# ARM-Cortex_M0.net
KiCad netlist of a schematic drawn in EAGLE
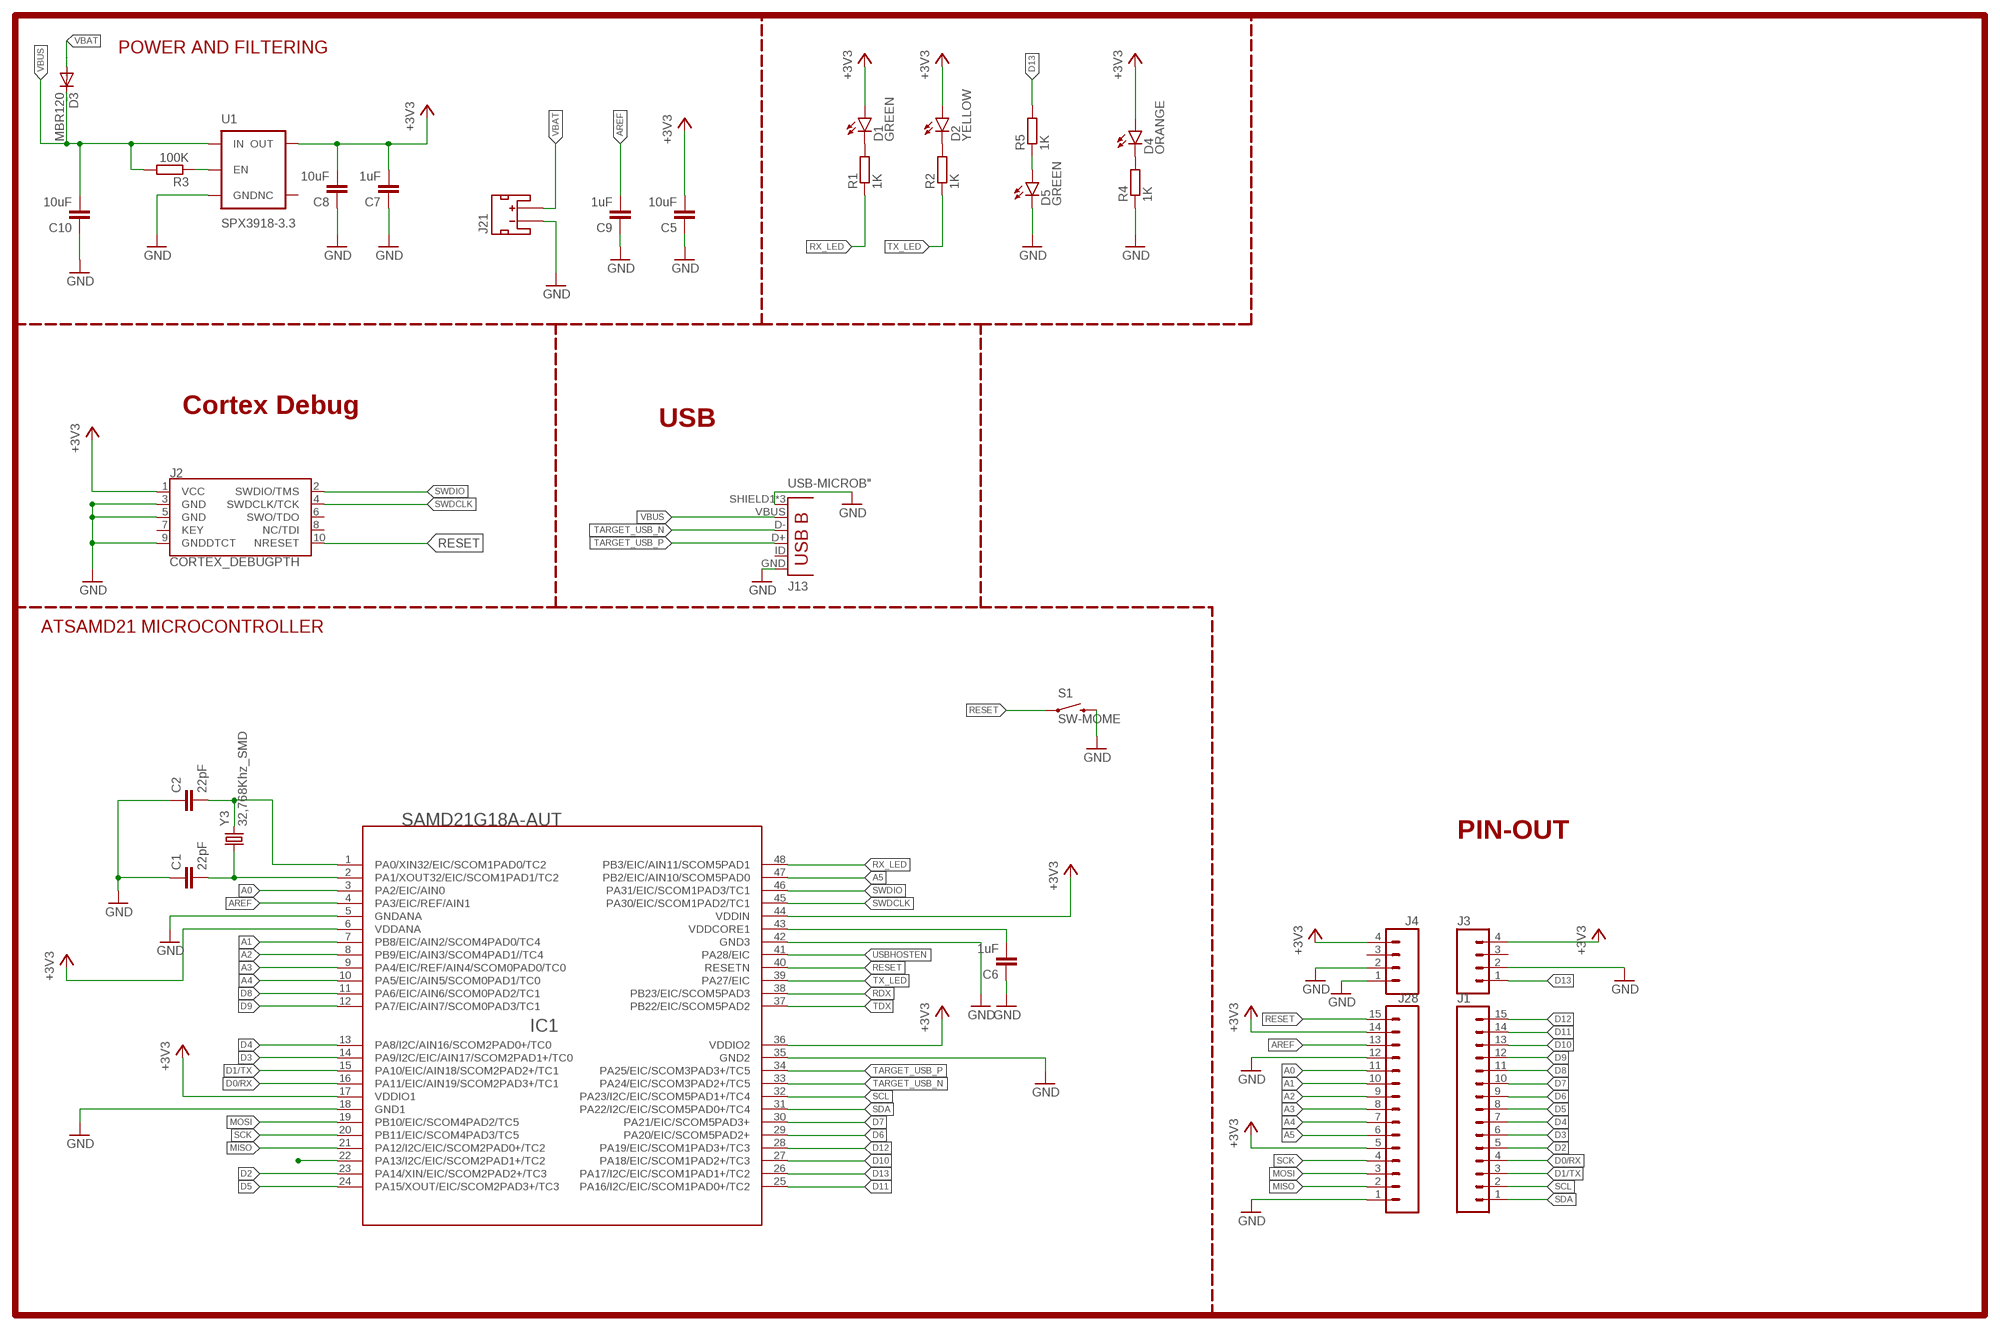
[diagram p0: schematic, sheet 1]

(export (version "E")
  (design (tool "Eeschema 10.0.6"))
  (components
    (comp (ref "C1")
      (value "22pF")
      (footprint "eagle-import:C0603")
      (libsource (lib "eagle-import") (part "C-EUC0603"))
    )
    (comp (ref "C2")
      (value "22pF")
      (footprint "eagle-import:C0603")
      (libsource (lib "eagle-import") (part "C-EUC0603"))
    )
    (comp (ref "C5")
      (value "10uF")
      (footprint "eagle-import:C0603")
      (libsource (lib "eagle-import") (part "C-EUC0603"))
    )
    (comp (ref "C6")
      (value "1uF")
      (footprint "eagle-import:C0603")
      (libsource (lib "eagle-import") (part "C-EUC0603"))
    )
    (comp (ref "C7")
      (value "1uF")
      (footprint "eagle-import:C0603")
      (libsource (lib "eagle-import") (part "C-EUC0603"))
    )
    (comp (ref "C8")
      (value "10uF")
      (footprint "eagle-import:C0603")
      (libsource (lib "eagle-import") (part "C-EUC0603"))
    )
    (comp (ref "C9")
      (value "1uF")
      (footprint "eagle-import:C0603")
      (libsource (lib "eagle-import") (part "C-EUC0603"))
    )
    (comp (ref "C10")
      (value "10uF")
      (footprint "eagle-import:C0603")
      (libsource (lib "eagle-import") (part "C-EUC0603"))
    )
    (comp (ref "D1")
      (value "GREEN")
      (footprint "eagle-import:LED-0603")
      (libsource (lib "eagle-import") (part "LED0603"))
    )
    (comp (ref "D2")
      (value "YELLOW")
      (footprint "eagle-import:LED-0603")
      (libsource (lib "eagle-import") (part "LED0603"))
    )
    (comp (ref "D3")
      (value "MBR120")
      (footprint "eagle-import:SOD-123_MINI-SMA")
      (libsource (lib "eagle-import") (part "CGRM400-G1"))
    )
    (comp (ref "D4")
      (value "ORANGE")
      (footprint "eagle-import:LED-0603")
      (libsource (lib "eagle-import") (part "LED0603"))
    )
    (comp (ref "D5")
      (value "GREEN")
      (footprint "eagle-import:LED-0603")
      (libsource (lib "eagle-import") (part "LED0603"))
    )
    (comp (ref "IC1")
      (value "SAMD21G18A-AUT")
      (footprint "eagle-import:TQFP48-7X7")
      (libsource (lib "eagle-import") (part "1792_SAMD21G18A-AUT"))
    )
    (comp (ref "J1")
      (value "M15")
      (footprint "eagle-import:1X15")
      (libsource (lib "eagle-import") (part "M15"))
    )
    (comp (ref "J2")
      (value "CORTEX_DEBUGPTH")
      (footprint "eagle-import:2X5-PTH-1.27MM")
      (libsource (lib "eagle-import") (part "CORTEX_DEBUGPTH"))
    )
    (comp (ref "J3")
      (value "M04NO_SILK_ALL_ROUND")
      (footprint "eagle-import:1X04_NO_SILK_ALL_ROUND")
      (libsource (lib "eagle-import") (part "M04NO_SILK_ALL_ROUND"))
    )
    (comp (ref "J4")
      (value "M04NO_SILK_ALL_ROUND")
      (footprint "eagle-import:1X04_NO_SILK_ALL_ROUND")
      (libsource (lib "eagle-import") (part "M04NO_SILK_ALL_ROUND"))
    )
    (comp (ref "J13")
      (value "USB-MICROB\"")
      (footprint "eagle-import:USB-B-MICRO-SMD_V03")
      (libsource (lib "eagle-import") (part "USB-MICROB{dblquote}"))
    )
    (comp (ref "J21")
      (value "JST_2MM_MALE")
      (footprint "eagle-import:JST-2-SMD")
      (libsource (lib "eagle-import") (part "JST_2MM_MALE"))
    )
    (comp (ref "J28")
      (value "M15")
      (footprint "eagle-import:1X15")
      (libsource (lib "eagle-import") (part "M15"))
    )
    (comp (ref "R1")
      (value "1K")
      (footprint "eagle-import:R0603")
      (libsource (lib "eagle-import") (part "R-EU_R0603"))
    )
    (comp (ref "R2")
      (value "1K")
      (footprint "eagle-import:R0603")
      (libsource (lib "eagle-import") (part "R-EU_R0603"))
    )
    (comp (ref "R3")
      (value "100K")
      (footprint "eagle-import:R0603")
      (libsource (lib "eagle-import") (part "R-EU_R0603"))
    )
    (comp (ref "R4")
      (value "1K")
      (footprint "eagle-import:R0603")
      (libsource (lib "eagle-import") (part "R-EU_R0603"))
    )
    (comp (ref "R5")
      (value "1K")
      (footprint "eagle-import:R0603")
      (libsource (lib "eagle-import") (part "R-EU_R0603"))
    )
    (comp (ref "S1")
      (value "SW-MOME")
      (footprint "eagle-import:TACTILE-SWITCH-SMD")
      (libsource (lib "eagle-import") (part "SWITCH-MOMENTARY-2SMD"))
    )
    (comp (ref "U1")
      (value "SPX3918-3.3")
      (footprint "eagle-import:SOT23-5")
      (libsource (lib "eagle-import") (part "V_REG_AP2112K-3.3V"))
    )
    (comp (ref "Y3")
      (value "32,768Khz_SMD")
      (footprint "eagle-import:CRYSTAL-TXC-7A")
      (libsource (lib "eagle-import") (part "CRYSTALTXC-7A"))
    )
  )
  (nets
    (net (code "1") (name "+3V3") (class "Default")
      (node (ref "C5") (pin "2") (pinfunction "2_2") (pintype "passive"))
      (node (ref "C7") (pin "2") (pinfunction "2_2") (pintype "passive"))
      (node (ref "C8") (pin "2") (pinfunction "2_2") (pintype "passive"))
      (node (ref "D1") (pin "A") (pinfunction "A_A") (pintype "passive"))
      (node (ref "D2") (pin "A") (pinfunction "A_A") (pintype "passive"))
      (node (ref "D4") (pin "A") (pinfunction "A_A") (pintype "passive"))
      (node (ref "IC1") (pin "17") (pinfunction "VDDIO1_17") (pintype "power_in"))
      (node (ref "IC1") (pin "36") (pinfunction "VDDIO2_36") (pintype "power_in"))
      (node (ref "IC1") (pin "44") (pinfunction "VDDIN_44") (pintype "power_in"))
      (node (ref "IC1") (pin "6") (pinfunction "VDDANA_6") (pintype "power_in"))
      (node (ref "J2") (pin "1") (pinfunction "VCC_1") (pintype "bidirectional"))
      (node (ref "J28") (pin "14") (pinfunction "14_14") (pintype "passive"))
      (node (ref "J28") (pin "5") (pinfunction "5_5") (pintype "passive"))
      (node (ref "J3") (pin "4") (pinfunction "4_4") (pintype "passive"))
      (node (ref "J4") (pin "4") (pinfunction "4_4") (pintype "passive"))
      (node (ref "U1") (pin "5") (pinfunction "OUT_5") (pintype "passive"))
    )
    (net (code "2") (name "A0") (class "Default")
      (node (ref "IC1") (pin "3") (pinfunction "PA2/EIC/AIN0_3") (pintype "bidirectional"))
      (node (ref "J28") (pin "11") (pinfunction "11_11") (pintype "passive"))
    )
    (net (code "3") (name "A1") (class "Default")
      (node (ref "IC1") (pin "7") (pinfunction "PB8/EIC/AIN2/SCOM4PAD0/TC4_7") (pintype "bidirectional"))
      (node (ref "J28") (pin "10") (pinfunction "10_10") (pintype "passive"))
    )
    (net (code "4") (name "A2") (class "Default")
      (node (ref "IC1") (pin "8") (pinfunction "PB9/EIC/AIN3/SCOM4PAD1//TC4_8") (pintype "bidirectional"))
      (node (ref "J28") (pin "9") (pinfunction "9_9") (pintype "passive"))
    )
    (net (code "5") (name "A3") (class "Default")
      (node (ref "IC1") (pin "9") (pinfunction "PA4/EIC/REF/AIN4/SCOM0PAD0/TC0_9") (pintype "bidirectional"))
      (node (ref "J28") (pin "8") (pinfunction "8_8") (pintype "passive"))
    )
    (net (code "6") (name "A4") (class "Default")
      (node (ref "IC1") (pin "10") (pinfunction "PA5/EIC/AIN5/SCOM0PAD1/TC0_10") (pintype "bidirectional"))
      (node (ref "J28") (pin "7") (pinfunction "7_7") (pintype "passive"))
    )
    (net (code "7") (name "A5") (class "Default")
      (node (ref "IC1") (pin "47") (pinfunction "PB2/EIC/AIN10/SCOM5PAD0_47") (pintype "bidirectional"))
      (node (ref "J28") (pin "6") (pinfunction "6_6") (pintype "passive"))
    )
    (net (code "8") (name "AREF") (class "Default")
      (node (ref "C9") (pin "2") (pinfunction "2_2") (pintype "passive"))
      (node (ref "IC1") (pin "4") (pinfunction "PA3/EIC/REF/AIN1_4") (pintype "bidirectional"))
      (node (ref "J28") (pin "13") (pinfunction "13_13") (pintype "passive"))
    )
    (net (code "9") (name "D0{slash}RX") (class "Default")
      (node (ref "IC1") (pin "16") (pinfunction "PA11/EIC/AIN19/SCOM2PAD3+/TC1_16") (pintype "bidirectional"))
      (node (ref "J1") (pin "4") (pinfunction "4_4") (pintype "passive"))
    )
    (net (code "10") (name "D1{slash}TX") (class "Default")
      (node (ref "IC1") (pin "15") (pinfunction "PA10/EIC/AIN18/SCOM2PAD2+/TC1_15") (pintype "bidirectional"))
      (node (ref "J1") (pin "3") (pinfunction "3_3") (pintype "passive"))
    )
    (net (code "11") (name "D2") (class "Default")
      (node (ref "IC1") (pin "23") (pinfunction "PA14/XIN/EIC/SCOM2PAD2+/TC3_23") (pintype "bidirectional"))
      (node (ref "J1") (pin "5") (pinfunction "5_5") (pintype "passive"))
    )
    (net (code "12") (name "D3") (class "Default")
      (node (ref "IC1") (pin "14") (pinfunction "PA9/I2C/EIC/AIN17/SCOM2PAD1+/TC0_14") (pintype "bidirectional"))
      (node (ref "J1") (pin "6") (pinfunction "6_6") (pintype "passive"))
    )
    (net (code "13") (name "D4") (class "Default")
      (node (ref "IC1") (pin "13") (pinfunction "PA8/I2C/AIN16/SCOM2PAD0+/TC0_13") (pintype "bidirectional"))
      (node (ref "J1") (pin "7") (pinfunction "7_7") (pintype "passive"))
    )
    (net (code "14") (name "D5") (class "Default")
      (node (ref "IC1") (pin "24") (pinfunction "PA15/XOUT/EIC/SCOM2PAD3+/TC3_24") (pintype "bidirectional"))
      (node (ref "J1") (pin "8") (pinfunction "8_8") (pintype "passive"))
    )
    (net (code "15") (name "D6") (class "Default")
      (node (ref "IC1") (pin "29") (pinfunction "PA20/EIC/SCOM5PAD2+_29") (pintype "bidirectional"))
      (node (ref "J1") (pin "9") (pinfunction "9_9") (pintype "passive"))
    )
    (net (code "16") (name "D7") (class "Default")
      (node (ref "IC1") (pin "30") (pinfunction "PA21/EIC/SCOM5PAD3+_30") (pintype "bidirectional"))
      (node (ref "J1") (pin "10") (pinfunction "10_10") (pintype "passive"))
    )
    (net (code "17") (name "D8") (class "Default")
      (node (ref "IC1") (pin "11") (pinfunction "PA6/EIC/AIN6/SCOM0PAD2/TC1_11") (pintype "bidirectional"))
      (node (ref "J1") (pin "11") (pinfunction "11_11") (pintype "passive"))
    )
    (net (code "18") (name "D9") (class "Default")
      (node (ref "IC1") (pin "12") (pinfunction "PA7/EIC/AIN7/SCOM0PAD3/TC1_12") (pintype "bidirectional"))
      (node (ref "J1") (pin "12") (pinfunction "12_12") (pintype "passive"))
    )
    (net (code "19") (name "D10") (class "Default")
      (node (ref "IC1") (pin "27") (pinfunction "PA18/EIC/SCOM1PAD2+/TC3_27") (pintype "bidirectional"))
      (node (ref "J1") (pin "13") (pinfunction "13_13") (pintype "passive"))
    )
    (net (code "20") (name "D11") (class "Default")
      (node (ref "IC1") (pin "25") (pinfunction "PA16/I2C/EIC/SCOM1PAD0+/TC2_25") (pintype "bidirectional"))
      (node (ref "J1") (pin "14") (pinfunction "14_14") (pintype "passive"))
    )
    (net (code "21") (name "D12") (class "Default")
      (node (ref "IC1") (pin "28") (pinfunction "PA19/EIC/SCOM1PAD3+/TC3_28") (pintype "bidirectional"))
      (node (ref "J1") (pin "15") (pinfunction "15_15") (pintype "passive"))
    )
    (net (code "22") (name "D13") (class "Default")
      (node (ref "IC1") (pin "26") (pinfunction "PA17/I2C/EIC/SCOM1PAD1+/TC2_26") (pintype "bidirectional"))
      (node (ref "J3") (pin "1") (pinfunction "1_1") (pintype "passive"))
      (node (ref "R5") (pin "2") (pinfunction "2_2") (pintype "passive"))
    )
    (net (code "23") (name "GND") (class "Default")
      (node (ref "C1") (pin "1") (pinfunction "1_1") (pintype "passive"))
      (node (ref "C10") (pin "1") (pinfunction "1_1") (pintype "passive"))
      (node (ref "C2") (pin "1") (pinfunction "1_1") (pintype "passive"))
      (node (ref "C5") (pin "1") (pinfunction "1_1") (pintype "passive"))
      (node (ref "C6") (pin "1") (pinfunction "1_1") (pintype "passive"))
      (node (ref "C7") (pin "1") (pinfunction "1_1") (pintype "passive"))
      (node (ref "C8") (pin "1") (pinfunction "1_1") (pintype "passive"))
      (node (ref "C9") (pin "1") (pinfunction "1_1") (pintype "passive"))
      (node (ref "D5") (pin "C") (pinfunction "C_C") (pintype "passive"))
      (node (ref "IC1") (pin "18") (pinfunction "GND1_18") (pintype "power_in"))
      (node (ref "IC1") (pin "35") (pinfunction "GND2_35") (pintype "power_in"))
      (node (ref "IC1") (pin "42") (pinfunction "GND3_42") (pintype "power_in"))
      (node (ref "IC1") (pin "5") (pinfunction "GNDANA_5") (pintype "power_in"))
      (node (ref "J13") (pin "GND") (pinfunction "GND_GND") (pintype "bidirectional"))
      (node (ref "J13") (pin "SHIELD1") (pinfunction "SHIELD_SHIELD1") (pintype "bidirectional"))
      (node (ref "J13") (pin "SHIELD2") (pinfunction "SHIELD_SHIELD2") (pintype "bidirectional"))
      (node (ref "J13") (pin "SHIELD3") (pinfunction "SHIELD_SHIELD3") (pintype "bidirectional"))
      (node (ref "J2") (pin "3") (pinfunction "GND_3") (pintype "bidirectional"))
      (node (ref "J2") (pin "5") (pinfunction "GND_5") (pintype "bidirectional"))
      (node (ref "J2") (pin "9") (pinfunction "GNDDTCT_9") (pintype "bidirectional"))
      (node (ref "J21") (pin "1") (pinfunction "-_1") (pintype "bidirectional"))
      (node (ref "J28") (pin "1") (pinfunction "1_1") (pintype "passive"))
      (node (ref "J28") (pin "12") (pinfunction "12_12") (pintype "passive"))
      (node (ref "J3") (pin "2") (pinfunction "2_2") (pintype "passive"))
      (node (ref "J4") (pin "1") (pinfunction "1_1") (pintype "passive"))
      (node (ref "J4") (pin "2") (pinfunction "2_2") (pintype "passive"))
      (node (ref "R4") (pin "1") (pinfunction "1_1") (pintype "passive"))
      (node (ref "S1") (pin "3") (pinfunction "2_3") (pintype "passive"))
      (node (ref "U1") (pin "2") (pinfunction "GND_2") (pintype "input"))
    )
    (net (code "24") (name "MISO") (class "Default")
      (node (ref "IC1") (pin "21") (pinfunction "PA12/I2C/EIC/SCOM2PAD0+/TC2_21") (pintype "bidirectional"))
      (node (ref "J28") (pin "2") (pinfunction "2_2") (pintype "passive"))
    )
    (net (code "25") (name "MOSI") (class "Default")
      (node (ref "IC1") (pin "19") (pinfunction "PB10/EIC/SCOM4PAD2/TC5_19") (pintype "bidirectional"))
      (node (ref "J28") (pin "3") (pinfunction "3_3") (pintype "passive"))
    )
    (net (code "26") (name "Net-(D1-PadC)") (class "Default")
      (node (ref "D1") (pin "C") (pinfunction "C_C") (pintype "passive"))
      (node (ref "R1") (pin "2") (pinfunction "2_2") (pintype "passive"))
    )
    (net (code "27") (name "Net-(D2-PadC)") (class "Default")
      (node (ref "D2") (pin "C") (pinfunction "C_C") (pintype "passive"))
      (node (ref "R2") (pin "2") (pinfunction "2_2") (pintype "passive"))
    )
    (net (code "28") (name "Net-(D4-PadC)") (class "Default")
      (node (ref "D4") (pin "C") (pinfunction "C_C") (pintype "passive"))
      (node (ref "R4") (pin "2") (pinfunction "2_2") (pintype "passive"))
    )
    (net (code "29") (name "Net-(D5-PadA)") (class "Default")
      (node (ref "D5") (pin "A") (pinfunction "A_A") (pintype "passive"))
      (node (ref "R5") (pin "1") (pinfunction "1_1") (pintype "passive"))
    )
    (net (code "30") (name "Net-(IC1-PA0{slash}XIN32{slash}EIC{slash}SCOM1PAD0{slash}TC2)") (class "Default")
      (node (ref "C2") (pin "2") (pinfunction "2_2") (pintype "passive"))
      (node (ref "IC1") (pin "1") (pinfunction "PA0/XIN32/EIC/SCOM1PAD0/TC2_1") (pintype "bidirectional"))
      (node (ref "Y3") (pin "P$2") (pinfunction "2_P$2") (pintype "passive"))
    )
    (net (code "31") (name "Net-(IC1-PA1{slash}XOUT32{slash}EIC{slash}SCOM1PAD1{slash}TC2)") (class "Default")
      (node (ref "C1") (pin "2") (pinfunction "2_2") (pintype "passive"))
      (node (ref "IC1") (pin "2") (pinfunction "PA1/XOUT32/EIC/SCOM1PAD1/TC2_2") (pintype "bidirectional"))
      (node (ref "Y3") (pin "P$1") (pinfunction "1_P$1") (pintype "passive"))
    )
    (net (code "32") (name "Net-(IC1-VDDCORE1)") (class "Default")
      (node (ref "C6") (pin "2") (pinfunction "2_2") (pintype "passive"))
      (node (ref "IC1") (pin "43") (pinfunction "VDDCORE1_43") (pintype "input"))
    )
    (net (code "33") (name "Net-(U1-EN)") (class "Default")
      (node (ref "R3") (pin "1") (pinfunction "1_1") (pintype "passive"))
      (node (ref "U1") (pin "3") (pinfunction "EN_3") (pintype "input"))
    )
    (net (code "34") (name "RDX") (class "Default")
      (node (ref "IC1") (pin "38") (pinfunction "PB23/EIC/SCOM5PAD3_38") (pintype "bidirectional"))
    )
    (net (code "35") (name "RESET") (class "Default")
      (node (ref "IC1") (pin "40") (pinfunction "RESETN_40") (pintype "bidirectional"))
      (node (ref "J2") (pin "10") (pinfunction "NRESET_10") (pintype "bidirectional"))
      (node (ref "J28") (pin "15") (pinfunction "15_15") (pintype "passive"))
      (node (ref "S1") (pin "1") (pinfunction "1_1") (pintype "passive"))
    )
    (net (code "36") (name "RX_LED") (class "Default")
      (node (ref "IC1") (pin "48") (pinfunction "PB3/EIC/AIN11/SCOM5PAD1_48") (pintype "bidirectional"))
      (node (ref "R1") (pin "1") (pinfunction "1_1") (pintype "passive"))
    )
    (net (code "37") (name "SCK") (class "Default")
      (node (ref "IC1") (pin "20") (pinfunction "PB11/EIC/SCOM4PAD3/TC5_20") (pintype "bidirectional"))
      (node (ref "J28") (pin "4") (pinfunction "4_4") (pintype "passive"))
    )
    (net (code "38") (name "SCL") (class "Default")
      (node (ref "IC1") (pin "32") (pinfunction "PA23/I2C/EIC/SCOM5PAD1+/TC4_32") (pintype "bidirectional"))
      (node (ref "J1") (pin "2") (pinfunction "2_2") (pintype "passive"))
    )
    (net (code "39") (name "SDA") (class "Default")
      (node (ref "IC1") (pin "31") (pinfunction "PA22/I2C/EIC/SCOM5PAD0+/TC4_31") (pintype "bidirectional"))
      (node (ref "J1") (pin "1") (pinfunction "1_1") (pintype "passive"))
    )
    (net (code "40") (name "SWDCLK") (class "Default")
      (node (ref "IC1") (pin "45") (pinfunction "PA30/EIC/SCOM1PAD2/TC1_45") (pintype "bidirectional"))
      (node (ref "J2") (pin "4") (pinfunction "SWDCLK/TCK_4") (pintype "bidirectional"))
    )
    (net (code "41") (name "SWDIO") (class "Default")
      (node (ref "IC1") (pin "46") (pinfunction "PA31/EIC/SCOM1PAD3/TC1_46") (pintype "bidirectional"))
      (node (ref "J2") (pin "2") (pinfunction "SWDIO/TMS_2") (pintype "bidirectional"))
    )
    (net (code "42") (name "TARGET_USB_N") (class "Default")
      (node (ref "IC1") (pin "33") (pinfunction "PA24/EIC/SCOM3PAD2+/TC5_33") (pintype "bidirectional"))
      (node (ref "J13") (pin "D-") (pinfunction "D-_D-") (pintype "bidirectional"))
    )
    (net (code "43") (name "TARGET_USB_P") (class "Default")
      (node (ref "IC1") (pin "34") (pinfunction "PA25/EIC/SCOM3PAD3+/TC5_34") (pintype "bidirectional"))
      (node (ref "J13") (pin "D+") (pinfunction "D+_D+") (pintype "bidirectional"))
    )
    (net (code "44") (name "TDX") (class "Default")
      (node (ref "IC1") (pin "37") (pinfunction "PB22/EIC/SCOM5PAD2_37") (pintype "bidirectional"))
    )
    (net (code "45") (name "TX_LED") (class "Default")
      (node (ref "IC1") (pin "39") (pinfunction "PA27/EIC_39") (pintype "bidirectional"))
      (node (ref "R2") (pin "1") (pinfunction "1_1") (pintype "passive"))
    )
    (net (code "46") (name "USBHOSTEN") (class "Default")
      (node (ref "IC1") (pin "41") (pinfunction "PA28/EIC_41") (pintype "bidirectional"))
    )
    (net (code "47") (name "VBAT") (class "Default")
      (node (ref "D3") (pin "A") (pinfunction "A_A") (pintype "passive"))
      (node (ref "J21") (pin "2") (pinfunction "+_2") (pintype "bidirectional"))
    )
    (net (code "48") (name "VBUS") (class "Default")
      (node (ref "C10") (pin "2") (pinfunction "2_2") (pintype "passive"))
      (node (ref "D3") (pin "C") (pinfunction "C_C") (pintype "passive"))
      (node (ref "J13") (pin "VBUS") (pinfunction "VBUS_VBUS") (pintype "bidirectional"))
      (node (ref "R3") (pin "2") (pinfunction "2_2") (pintype "passive"))
      (node (ref "U1") (pin "1") (pinfunction "IN_1") (pintype "input"))
    )
    (net (code "49") (name "unconnected-(IC1-PA13{slash}I2C{slash}EIC{slash}SCOM2PAD1+{slash}TC2-Pad22)") (class "Default")
      (node (ref "IC1") (pin "22") (pinfunction "PA13/I2C/EIC/SCOM2PAD1+/TC2_22") (pintype "bidirectional"))
    )
    (net (code "50") (name "unconnected-(J2-KEY-Pad7)") (class "Default")
      (node (ref "J2") (pin "7") (pinfunction "KEY_7") (pintype "bidirectional"))
    )
    (net (code "51") (name "unconnected-(J2-NC{slash}TDI-Pad8)") (class "Default")
      (node (ref "J2") (pin "8") (pinfunction "NC/TDI_8") (pintype "bidirectional"))
    )
    (net (code "52") (name "unconnected-(J2-SWO{slash}TDO-Pad6)") (class "Default")
      (node (ref "J2") (pin "6") (pinfunction "SWO/TDO_6") (pintype "bidirectional"))
    )
    (net (code "53") (name "unconnected-(J3-Pad3)") (class "Default")
      (node (ref "J3") (pin "3") (pinfunction "3_3") (pintype "passive"))
    )
    (net (code "54") (name "unconnected-(J4-Pad3)") (class "Default")
      (node (ref "J4") (pin "3") (pinfunction "3_3") (pintype "passive"))
    )
    (net (code "55") (name "unconnected-(J13-USBID-PadID)") (class "Default")
      (node (ref "J13") (pin "ID") (pinfunction "USBID_ID") (pintype "bidirectional"))
    )
    (net (code "56") (name "unconnected-(J21-PAD1-PadNC1)") (class "Default")
      (node (ref "J21") (pin "NC1") (pinfunction "PAD1_NC1") (pintype "bidirectional"))
    )
    (net (code "57") (name "unconnected-(J21-PAD2-PadNC2)") (class "Default")
      (node (ref "J21") (pin "NC2") (pinfunction "PAD2_NC2") (pintype "bidirectional"))
    )
    (net (code "58") (name "unconnected-(U1-NC-Pad4)") (class "Default")
      (node (ref "U1") (pin "4") (pinfunction "NC_4") (pintype "input"))
    )
  )
)
